# SensorHub_R2.net
KiCad netlist of a schematic drawn in EAGLE
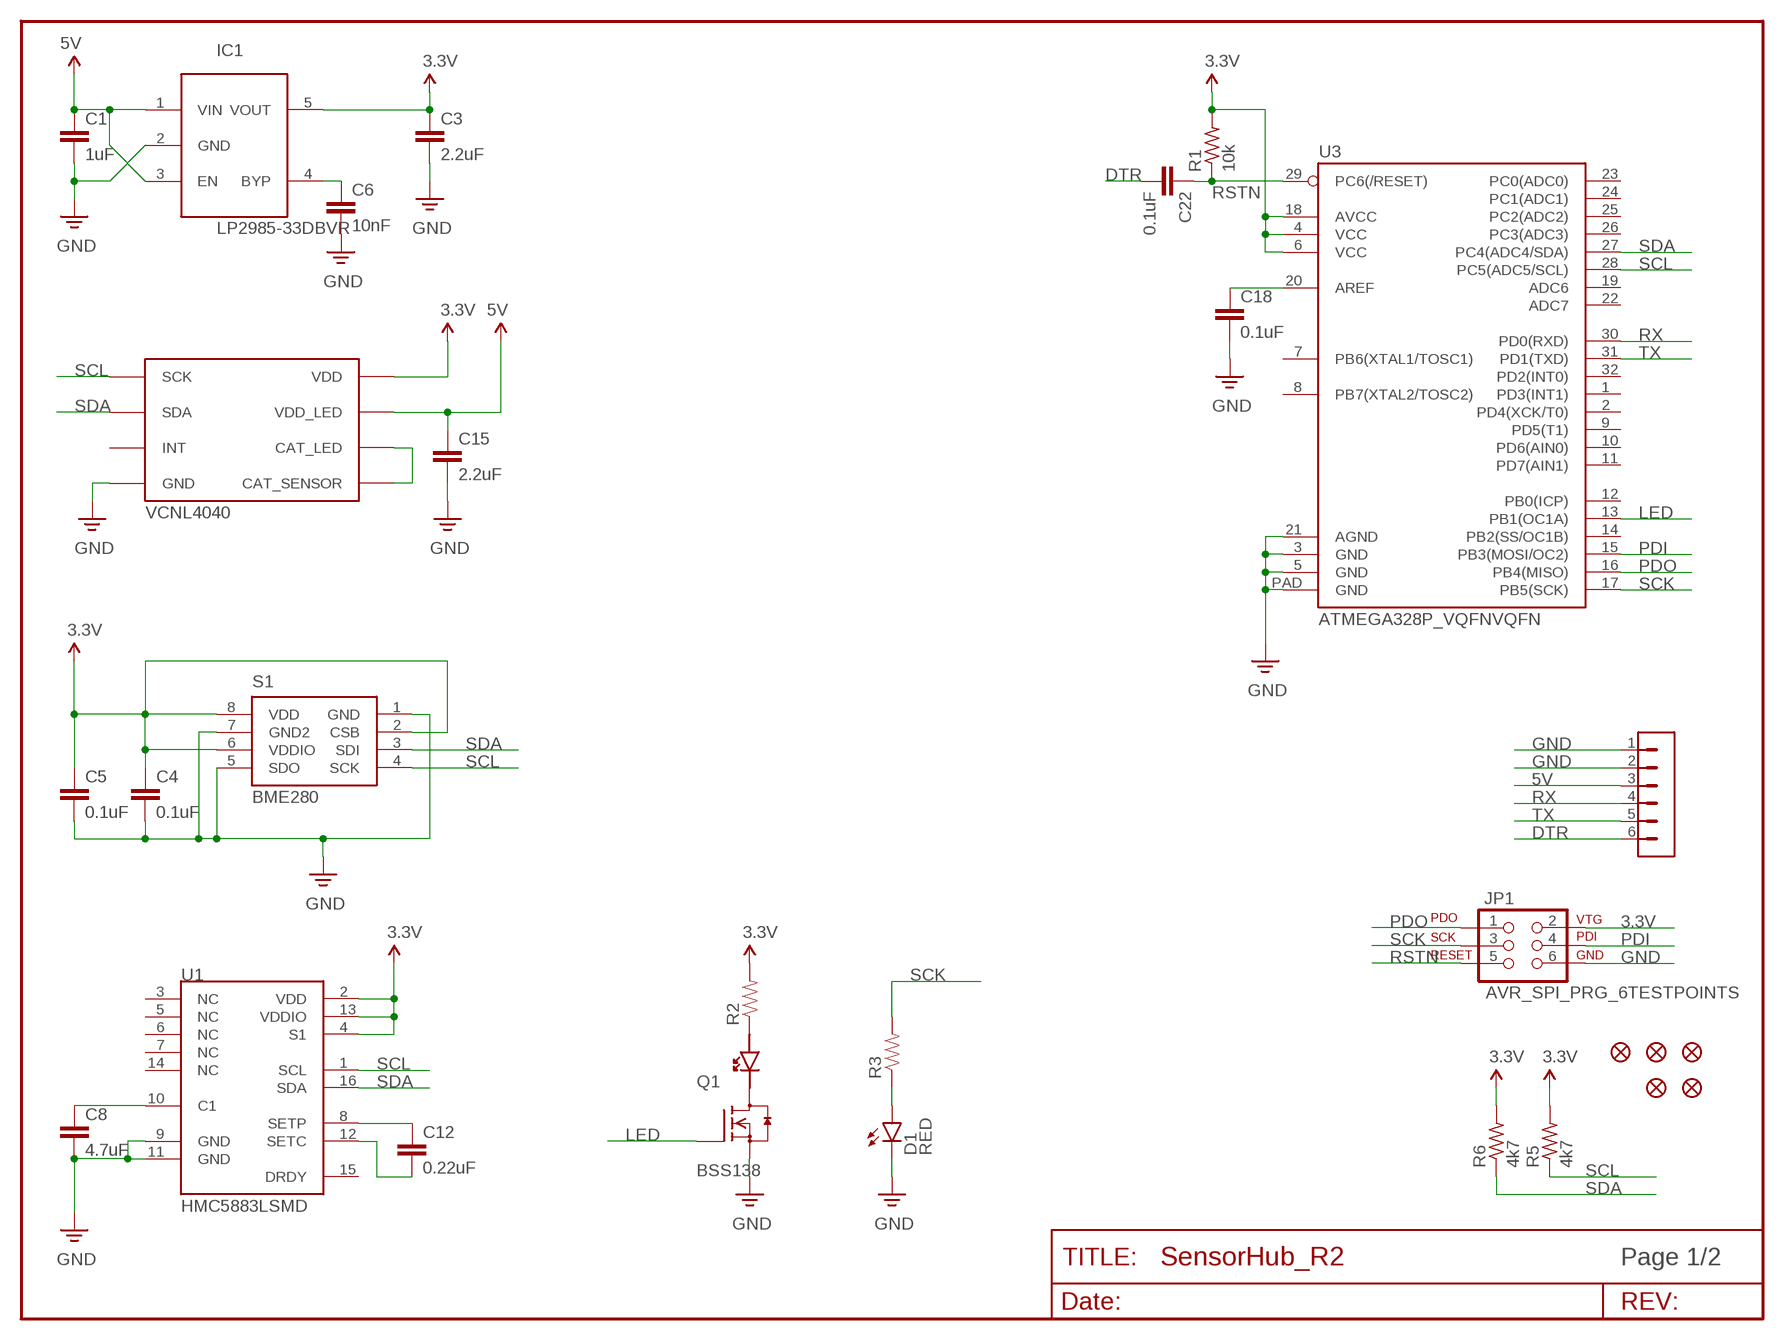
[diagram p0: schematic, sheet 1]

(export (version "E")
  (design (tool "Eeschema 10.0.6"))
  (components
    (comp (ref "C1")
      (value "1uF")
      (footprint "eagle-import:0603-CAP")
      (libsource (lib "eagle-import") (part "CAP0603-CAP"))
    )
    (comp (ref "C3")
      (value "2.2uF")
      (footprint "eagle-import:0603-CAP")
      (libsource (lib "eagle-import") (part "CAP0603-CAP"))
    )
    (comp (ref "C4")
      (value "0.1uF")
      (footprint "eagle-import:0603-CAP")
      (libsource (lib "eagle-import") (part "CAP0603-CAP"))
    )
    (comp (ref "C5")
      (value "0.1uF")
      (footprint "eagle-import:0603-CAP")
      (libsource (lib "eagle-import") (part "CAP0603-CAP"))
    )
    (comp (ref "C6")
      (value "10nF")
      (footprint "eagle-import:0603-CAP")
      (libsource (lib "eagle-import") (part "CAP0603-CAP"))
    )
    (comp (ref "C8")
      (value "4.7uF")
      (footprint "eagle-import:0603-CAP")
      (libsource (lib "eagle-import") (part "CAP0603-CAP"))
    )
    (comp (ref "C12")
      (value "0.22uF")
      (footprint "eagle-import:0603-CAP")
      (libsource (lib "eagle-import") (part "CAP0603-CAP"))
    )
    (comp (ref "C15")
      (value "2.2uF")
      (footprint "eagle-import:0603-CAP")
      (libsource (lib "eagle-import") (part "CAP0603-CAP"))
    )
    (comp (ref "C18")
      (value "0.1uF")
      (footprint "eagle-import:0603-CAP")
      (libsource (lib "eagle-import") (part "CAP0603-CAP"))
    )
    (comp (ref "C22")
      (value "0.1uF")
      (footprint "eagle-import:0603-CAP")
      (libsource (lib "eagle-import") (part "CAP0603-CAP"))
    )
    (comp (ref "D1")
      (value "RED")
      (footprint "eagle-import:LED-0603")
      (libsource (lib "eagle-import") (part "LED-RED0603"))
    )
    (comp (ref "FID1")
      (value "FIDUCIALUFIDUCIAL")
      (footprint "eagle-import:MICRO-FIDUCIAL")
      (libsource (lib "eagle-import") (part "FIDUCIALUFIDUCIAL"))
    )
    (comp (ref "FID2")
      (value "FIDUCIALUFIDUCIAL")
      (footprint "eagle-import:MICRO-FIDUCIAL")
      (libsource (lib "eagle-import") (part "FIDUCIALUFIDUCIAL"))
    )
    (comp (ref "FID3")
      (value "FIDUCIALUFIDUCIAL")
      (footprint "eagle-import:MICRO-FIDUCIAL")
      (libsource (lib "eagle-import") (part "FIDUCIALUFIDUCIAL"))
    )
    (comp (ref "FID4")
      (value "FIDUCIALUFIDUCIAL")
      (footprint "eagle-import:MICRO-FIDUCIAL")
      (libsource (lib "eagle-import") (part "FIDUCIALUFIDUCIAL"))
    )
    (comp (ref "FID5")
      (value "FIDUCIALUFIDUCIAL")
      (footprint "eagle-import:MICRO-FIDUCIAL")
      (libsource (lib "eagle-import") (part "FIDUCIALUFIDUCIAL"))
    )
    (comp (ref "IC1")
      (value "LP2985-33DBVR")
      (footprint "eagle-import:SOT23-5L")
      (libsource (lib "eagle-import") (part "LP298XS"))
    )
    (comp (ref "JP1")
      (value "AVR_SPI_PRG_6TESTPOINTS")
      (footprint "eagle-import:2X3_TEST_POINTS")
      (libsource (lib "eagle-import") (part "AVR_SPI_PRG_6TESTPOINTS"))
    )
    (comp (ref "Q1")
      (value "BSS138")
      (footprint "eagle-import:SOT23")
      (libsource (lib "eagle-import") (part "BSS138"))
    )
    (comp (ref "R1")
      (value "10k")
      (footprint "eagle-import:R0603")
      (libsource (lib "eagle-import") (part "R-US_R0603"))
    )
    (comp (ref "R2")
      (value "RESISTOR0603")
      (footprint "eagle-import:0603-RES")
      (libsource (lib "eagle-import") (part "RESISTOR0603"))
    )
    (comp (ref "R3")
      (value "RESISTOR0603")
      (footprint "eagle-import:0603-RES")
      (libsource (lib "eagle-import") (part "RESISTOR0603"))
    )
    (comp (ref "R5")
      (value "4k7")
      (footprint "eagle-import:R0603")
      (libsource (lib "eagle-import") (part "R-US_R0603"))
    )
    (comp (ref "R6")
      (value "4k7")
      (footprint "eagle-import:R0603")
      (libsource (lib "eagle-import") (part "R-US_R0603"))
    )
    (comp (ref "S1")
      (value "BME280")
      (footprint "eagle-import:BME280")
      (libsource (lib "eagle-import") (part "BME280"))
    )
    (comp (ref "U$1")
      (value "M06-LONG")
      (footprint "eagle-import:M06-LONG")
      (libsource (lib "eagle-import") (part "M06-LONG"))
    )
    (comp (ref "U$3")
      (value "VCNL4040")
      (footprint "eagle-import:VCNL4040")
      (libsource (lib "eagle-import") (part "VCNL4040"))
    )
    (comp (ref "U$4")
      (value "PLCC_LED")
      (footprint "eagle-import:LED-PLCC")
      (libsource (lib "eagle-import") (part "PLCC_LED"))
    )
    (comp (ref "U1")
      (value "HMC5883LSMD")
      (footprint "eagle-import:16LPCC")
      (libsource (lib "eagle-import") (part "HMC5883LSMD"))
    )
    (comp (ref "U3")
      (value "ATMEGA328P_VQFNVQFN")
      (footprint "eagle-import:MLF32-PAD")
      (libsource (lib "eagle-import") (part "ATMEGA328P_MLFMLF32"))
    )
  )
  (nets
    (net (code "1") (name "/DTR") (class "Default")
      (node (ref "C22") (pin "2") (pinfunction "2_2") (pintype "passive"))
      (node (ref "U$1") (pin "6") (pinfunction "P$6_6") (pintype "bidirectional"))
    )
    (net (code "2") (name "/LED") (class "Default")
      (node (ref "Q1") (pin "1") (pinfunction "G_1") (pintype "passive"))
      (node (ref "U3") (pin "13") (pinfunction "PB1(OC1A)_13") (pintype "bidirectional"))
    )
    (net (code "3") (name "/PDI") (class "Default")
      (node (ref "JP1") (pin "4") (pinfunction "4_4") (pintype "passive"))
      (node (ref "U3") (pin "15") (pinfunction "PB3(MOSI/OC2)_15") (pintype "bidirectional"))
    )
    (net (code "4") (name "/PDO") (class "Default")
      (node (ref "JP1") (pin "1") (pinfunction "1_1") (pintype "passive"))
      (node (ref "U3") (pin "16") (pinfunction "PB4(MISO)_16") (pintype "bidirectional"))
    )
    (net (code "5") (name "/RSTN") (class "Default")
      (node (ref "C22") (pin "1") (pinfunction "1_1") (pintype "passive"))
      (node (ref "JP1") (pin "5") (pinfunction "5_5") (pintype "passive"))
      (node (ref "R1") (pin "1") (pinfunction "1_1") (pintype "passive"))
      (node (ref "U3") (pin "29") (pinfunction "PC6(/RESET)_29") (pintype "bidirectional"))
    )
    (net (code "6") (name "/RX") (class "Default")
      (node (ref "U$1") (pin "4") (pinfunction "P$4_4") (pintype "bidirectional"))
      (node (ref "U3") (pin "30") (pinfunction "PD0(RXD)_30") (pintype "bidirectional"))
    )
    (net (code "7") (name "/SCK") (class "Default")
      (node (ref "JP1") (pin "3") (pinfunction "3_3") (pintype "passive"))
      (node (ref "R3") (pin "2") (pinfunction "2_2") (pintype "passive"))
      (node (ref "U3") (pin "17") (pinfunction "PB5(SCK)_17") (pintype "bidirectional"))
    )
    (net (code "8") (name "/SCL") (class "Default")
      (node (ref "R5") (pin "1") (pinfunction "1_1") (pintype "passive"))
      (node (ref "S1") (pin "4") (pinfunction "SCK_4") (pintype "bidirectional"))
      (node (ref "U$3") (pin "8") (pinfunction "SCK_8") (pintype "bidirectional"))
      (node (ref "U1") (pin "1") (pinfunction "SCL_1") (pintype "bidirectional"))
      (node (ref "U3") (pin "28") (pinfunction "PC5(ADC5/SCL)_28") (pintype "bidirectional"))
    )
    (net (code "9") (name "/SDA") (class "Default")
      (node (ref "R6") (pin "1") (pinfunction "1_1") (pintype "passive"))
      (node (ref "S1") (pin "3") (pinfunction "SDI_3") (pintype "bidirectional"))
      (node (ref "U$3") (pin "7") (pinfunction "SDA_7") (pintype "bidirectional"))
      (node (ref "U1") (pin "16") (pinfunction "SDA_16") (pintype "bidirectional"))
      (node (ref "U3") (pin "27") (pinfunction "PC4(ADC4/SDA)_27") (pintype "bidirectional"))
    )
    (net (code "10") (name "/TX") (class "Default")
      (node (ref "U$1") (pin "5") (pinfunction "P$5_5") (pintype "bidirectional"))
      (node (ref "U3") (pin "31") (pinfunction "PD1(TXD)_31") (pintype "bidirectional"))
    )
    (net (code "11") (name "3.3V") (class "Default")
      (node (ref "C3") (pin "1") (pinfunction "1_1") (pintype "passive"))
      (node (ref "C4") (pin "1") (pinfunction "1_1") (pintype "passive"))
      (node (ref "C5") (pin "1") (pinfunction "1_1") (pintype "passive"))
      (node (ref "IC1") (pin "5") (pinfunction "VOUT_5") (pintype "bidirectional"))
      (node (ref "JP1") (pin "2") (pinfunction "2_2") (pintype "passive"))
      (node (ref "R1") (pin "2") (pinfunction "2_2") (pintype "passive"))
      (node (ref "R2") (pin "2") (pinfunction "2_2") (pintype "passive"))
      (node (ref "R5") (pin "2") (pinfunction "2_2") (pintype "passive"))
      (node (ref "R6") (pin "2") (pinfunction "2_2") (pintype "passive"))
      (node (ref "S1") (pin "2") (pinfunction "CSB_2") (pintype "bidirectional"))
      (node (ref "S1") (pin "6") (pinfunction "VDDIO_6") (pintype "bidirectional"))
      (node (ref "S1") (pin "8") (pinfunction "VDD_8") (pintype "bidirectional"))
      (node (ref "U$3") (pin "3") (pinfunction "VDD_3") (pintype "bidirectional"))
      (node (ref "U1") (pin "13") (pinfunction "VDDIO_13") (pintype "bidirectional"))
      (node (ref "U1") (pin "2") (pinfunction "VDD_2") (pintype "bidirectional"))
      (node (ref "U1") (pin "4") (pinfunction "S1_4") (pintype "bidirectional"))
      (node (ref "U3") (pin "18") (pinfunction "AVCC_18") (pintype "bidirectional"))
      (node (ref "U3") (pin "4") (pinfunction "VCC_4") (pintype "bidirectional"))
      (node (ref "U3") (pin "6") (pinfunction "VCC_6") (pintype "bidirectional"))
    )
    (net (code "12") (name "5V") (class "Default")
      (node (ref "C1") (pin "1") (pinfunction "1_1") (pintype "passive"))
      (node (ref "C15") (pin "1") (pinfunction "1_1") (pintype "passive"))
      (node (ref "IC1") (pin "1") (pinfunction "VIN_1") (pintype "bidirectional"))
      (node (ref "IC1") (pin "3") (pinfunction "EN_3") (pintype "bidirectional"))
      (node (ref "U$1") (pin "3") (pinfunction "P$3_3") (pintype "bidirectional"))
      (node (ref "U$3") (pin "4") (pinfunction "VDD_LED_4") (pintype "bidirectional"))
    )
    (net (code "13") (name "GND") (class "Default")
      (node (ref "C1") (pin "2") (pinfunction "2_2") (pintype "passive"))
      (node (ref "C15") (pin "2") (pinfunction "2_2") (pintype "passive"))
      (node (ref "C18") (pin "2") (pinfunction "2_2") (pintype "passive"))
      (node (ref "C3") (pin "2") (pinfunction "2_2") (pintype "passive"))
      (node (ref "C4") (pin "2") (pinfunction "2_2") (pintype "passive"))
      (node (ref "C5") (pin "2") (pinfunction "2_2") (pintype "passive"))
      (node (ref "C6") (pin "2") (pinfunction "2_2") (pintype "passive"))
      (node (ref "C8") (pin "2") (pinfunction "2_2") (pintype "passive"))
      (node (ref "D1") (pin "C") (pinfunction "C_C") (pintype "passive"))
      (node (ref "IC1") (pin "2") (pinfunction "GND_2") (pintype "bidirectional"))
      (node (ref "JP1") (pin "6") (pinfunction "6_6") (pintype "passive"))
      (node (ref "Q1") (pin "2") (pinfunction "S_2") (pintype "passive"))
      (node (ref "S1") (pin "1") (pinfunction "GND_1") (pintype "bidirectional"))
      (node (ref "S1") (pin "5") (pinfunction "SDO_5") (pintype "bidirectional"))
      (node (ref "S1") (pin "7") (pinfunction "GND2_7") (pintype "bidirectional"))
      (node (ref "U$1") (pin "1") (pinfunction "P$1_1") (pintype "bidirectional"))
      (node (ref "U$1") (pin "2") (pinfunction "P$2_2") (pintype "bidirectional"))
      (node (ref "U$3") (pin "1") (pinfunction "GND_1") (pintype "bidirectional"))
      (node (ref "U1") (pin "11") (pinfunction "GND_11") (pintype "bidirectional"))
      (node (ref "U1") (pin "9") (pinfunction "GND_9") (pintype "bidirectional"))
      (node (ref "U3") (pin "21") (pinfunction "AGND_21") (pintype "bidirectional"))
      (node (ref "U3") (pin "3") (pinfunction "GND_3") (pintype "bidirectional"))
      (node (ref "U3") (pin "5") (pinfunction "GND_5") (pintype "bidirectional"))
      (node (ref "U3") (pin "PAD") (pinfunction "GND_PAD") (pintype "bidirectional"))
    )
    (net (code "14") (name "Net-(D1-PadA)") (class "Default")
      (node (ref "D1") (pin "A") (pinfunction "A_A") (pintype "passive"))
      (node (ref "R3") (pin "1") (pinfunction "1_1") (pintype "passive"))
    )
    (net (code "15") (name "Net-(IC1-BYP)") (class "Default")
      (node (ref "C6") (pin "1") (pinfunction "1_1") (pintype "passive"))
      (node (ref "IC1") (pin "4") (pinfunction "BYP_4") (pintype "bidirectional"))
    )
    (net (code "16") (name "Net-(Q1-D)") (class "Default")
      (node (ref "Q1") (pin "3") (pinfunction "D_3") (pintype "passive"))
      (node (ref "U$4") (pin "CATHODE") (pinfunction "CATHODE_CATHODE") (pintype "bidirectional"))
    )
    (net (code "17") (name "Net-(R2-Pad1)") (class "Default")
      (node (ref "R2") (pin "1") (pinfunction "1_1") (pintype "passive"))
      (node (ref "U$4") (pin "ANODE") (pinfunction "ANODE_ANODE") (pintype "bidirectional"))
    )
    (net (code "18") (name "Net-(U$3-CAT_LED)") (class "Default")
      (node (ref "U$3") (pin "2") (pinfunction "CAT_SENSOR_2") (pintype "bidirectional"))
      (node (ref "U$3") (pin "5") (pinfunction "CAT_LED_5") (pintype "bidirectional"))
    )
    (net (code "19") (name "Net-(U1-C1)") (class "Default")
      (node (ref "C8") (pin "1") (pinfunction "1_1") (pintype "passive"))
      (node (ref "U1") (pin "10") (pinfunction "C1_10") (pintype "bidirectional"))
    )
    (net (code "20") (name "Net-(U1-SETC)") (class "Default")
      (node (ref "C12") (pin "2") (pinfunction "2_2") (pintype "passive"))
      (node (ref "U1") (pin "12") (pinfunction "SETC_12") (pintype "bidirectional"))
    )
    (net (code "21") (name "Net-(U1-SETP)") (class "Default")
      (node (ref "C12") (pin "1") (pinfunction "1_1") (pintype "passive"))
      (node (ref "U1") (pin "8") (pinfunction "SETP_8") (pintype "bidirectional"))
    )
    (net (code "22") (name "Net-(U3-AREF)") (class "Default")
      (node (ref "C18") (pin "1") (pinfunction "1_1") (pintype "passive"))
      (node (ref "U3") (pin "20") (pinfunction "AREF_20") (pintype "bidirectional"))
    )
    (net (code "23") (name "unconnected-(U$3-INT-Pad6)") (class "Default")
      (node (ref "U$3") (pin "6") (pinfunction "INT_6") (pintype "bidirectional"))
    )
    (net (code "24") (name "unconnected-(U1-DRDY-Pad15)") (class "Default")
      (node (ref "U1") (pin "15") (pinfunction "DRDY_15") (pintype "bidirectional"))
    )
    (net (code "25") (name "unconnected-(U1-NC-Pad3)") (class "Default")
      (node (ref "U1") (pin "3") (pinfunction "NC_3") (pintype "bidirectional"))
    )
    (net (code "26") (name "unconnected-(U1-NC-Pad5)") (class "Default")
      (node (ref "U1") (pin "5") (pinfunction "NC_5") (pintype "bidirectional"))
    )
    (net (code "27") (name "unconnected-(U1-NC-Pad6)") (class "Default")
      (node (ref "U1") (pin "6") (pinfunction "NC_6") (pintype "bidirectional"))
    )
    (net (code "28") (name "unconnected-(U1-NC-Pad7)") (class "Default")
      (node (ref "U1") (pin "7") (pinfunction "NC_7") (pintype "bidirectional"))
    )
    (net (code "29") (name "unconnected-(U1-NC-Pad14)") (class "Default")
      (node (ref "U1") (pin "14") (pinfunction "NC_14") (pintype "bidirectional"))
    )
    (net (code "30") (name "unconnected-(U3-ADC6-Pad19)") (class "Default")
      (node (ref "U3") (pin "19") (pinfunction "ADC6_19") (pintype "bidirectional"))
    )
    (net (code "31") (name "unconnected-(U3-ADC7-Pad22)") (class "Default")
      (node (ref "U3") (pin "22") (pinfunction "ADC7_22") (pintype "bidirectional"))
    )
    (net (code "32") (name "unconnected-(U3-PB0(ICP)-Pad12)") (class "Default")
      (node (ref "U3") (pin "12") (pinfunction "PB0(ICP)_12") (pintype "bidirectional"))
    )
    (net (code "33") (name "unconnected-(U3-PB2(SS{slash}OC1B)-Pad14)") (class "Default")
      (node (ref "U3") (pin "14") (pinfunction "PB2(SS/OC1B)_14") (pintype "bidirectional"))
    )
    (net (code "34") (name "unconnected-(U3-PB6(XTAL1{slash}TOSC1)-Pad7)") (class "Default")
      (node (ref "U3") (pin "7") (pinfunction "PB6(XTAL1/TOSC1)_7") (pintype "bidirectional"))
    )
    (net (code "35") (name "unconnected-(U3-PB7(XTAL2{slash}TOSC2)-Pad8)") (class "Default")
      (node (ref "U3") (pin "8") (pinfunction "PB7(XTAL2/TOSC2)_8") (pintype "bidirectional"))
    )
    (net (code "36") (name "unconnected-(U3-PC0(ADC0)-Pad23)") (class "Default")
      (node (ref "U3") (pin "23") (pinfunction "PC0(ADC0)_23") (pintype "bidirectional"))
    )
    (net (code "37") (name "unconnected-(U3-PC1(ADC1)-Pad24)") (class "Default")
      (node (ref "U3") (pin "24") (pinfunction "PC1(ADC1)_24") (pintype "bidirectional"))
    )
    (net (code "38") (name "unconnected-(U3-PC2(ADC2)-Pad25)") (class "Default")
      (node (ref "U3") (pin "25") (pinfunction "PC2(ADC2)_25") (pintype "bidirectional"))
    )
    (net (code "39") (name "unconnected-(U3-PC3(ADC3)-Pad26)") (class "Default")
      (node (ref "U3") (pin "26") (pinfunction "PC3(ADC3)_26") (pintype "bidirectional"))
    )
    (net (code "40") (name "unconnected-(U3-PD2(INT0)-Pad32)") (class "Default")
      (node (ref "U3") (pin "32") (pinfunction "PD2(INT0)_32") (pintype "bidirectional"))
    )
    (net (code "41") (name "unconnected-(U3-PD3(INT1)-Pad1)") (class "Default")
      (node (ref "U3") (pin "1") (pinfunction "PD3(INT1)_1") (pintype "bidirectional"))
    )
    (net (code "42") (name "unconnected-(U3-PD4(XCK{slash}T0)-Pad2)") (class "Default")
      (node (ref "U3") (pin "2") (pinfunction "PD4(XCK/T0)_2") (pintype "bidirectional"))
    )
    (net (code "43") (name "unconnected-(U3-PD5(T1)-Pad9)") (class "Default")
      (node (ref "U3") (pin "9") (pinfunction "PD5(T1)_9") (pintype "bidirectional"))
    )
    (net (code "44") (name "unconnected-(U3-PD6(AIN0)-Pad10)") (class "Default")
      (node (ref "U3") (pin "10") (pinfunction "PD6(AIN0)_10") (pintype "bidirectional"))
    )
    (net (code "45") (name "unconnected-(U3-PD7(AIN1)-Pad11)") (class "Default")
      (node (ref "U3") (pin "11") (pinfunction "PD7(AIN1)_11") (pintype "bidirectional"))
    )
  )
)
